# SENS_LEDS.net
KiCad netlist of a schematic drawn in Altium Designer
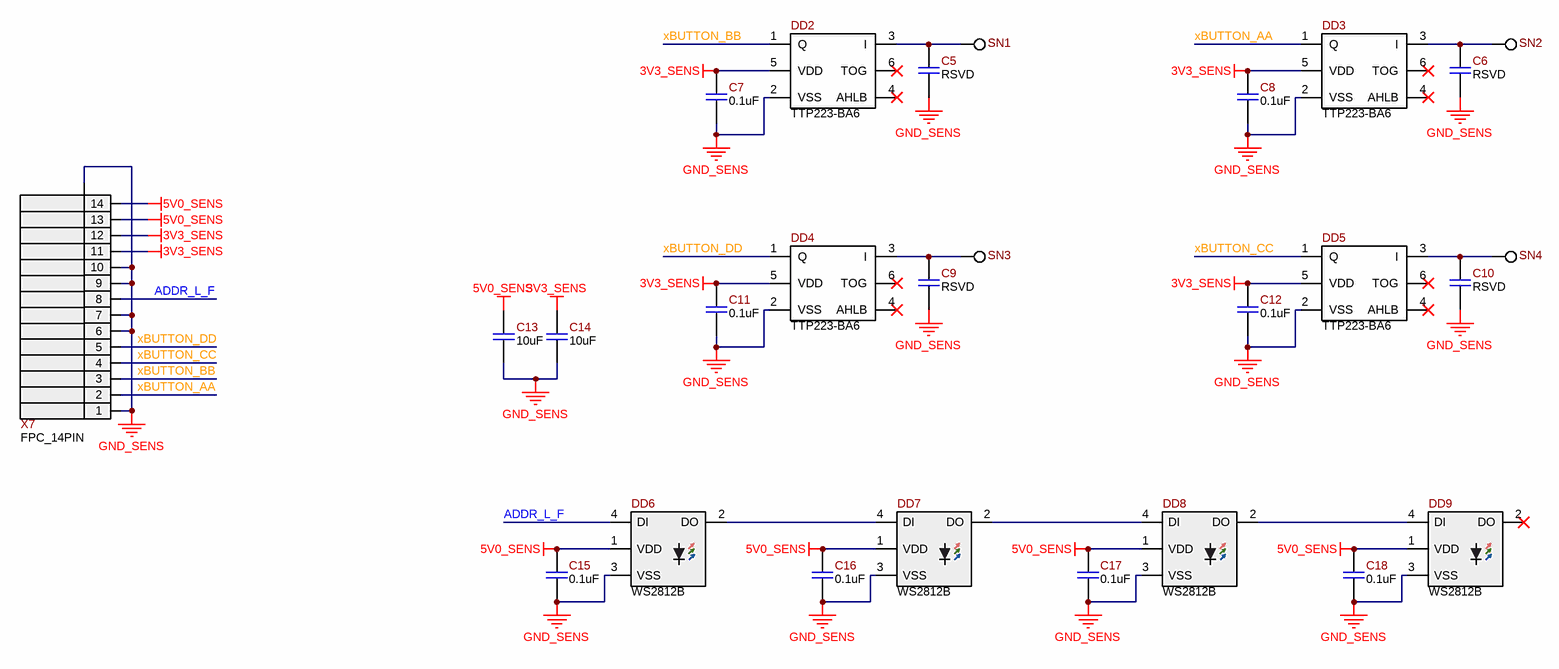
[diagram p0: SENS+LEDS.SchDoc]

(export (version "E")
  (design (tool "Eeschema 10.0.6"))
  (components
    (comp (ref "C5")
      (value "RSVD")
      (footprint "C0402(1005)")
      (description "CAP CER 0.1UF 25V X7R 0402")
      (fields (field (name "PART NUMBER") "0.1uF  25V C0402") (field (name "TOLERANCE") "±10%"))
      (libsource (lib "Database") (part "Capacitor_Ceramic"))
    )
    (comp (ref "C6")
      (value "RSVD")
      (footprint "C0402(1005)")
      (description "CAP CER 0.1UF 25V X7R 0402")
      (fields (field (name "PART NUMBER") "0.1uF  25V C0402") (field (name "TOLERANCE") "±10%"))
      (libsource (lib "Database") (part "Capacitor_Ceramic"))
    )
    (comp (ref "C7")
      (value "0.1uF")
      (footprint "C0402(1005)")
      (description "CAP CER 0.1UF 25V X7R 0402")
      (fields (field (name "PART NUMBER") "0.1uF  25V C0402") (field (name "TOLERANCE") "±10%"))
      (libsource (lib "Database") (part "Capacitor_Ceramic"))
    )
    (comp (ref "C8")
      (value "0.1uF")
      (footprint "C0402(1005)")
      (description "CAP CER 0.1UF 25V X7R 0402")
      (fields (field (name "PART NUMBER") "0.1uF  25V C0402") (field (name "TOLERANCE") "±10%"))
      (libsource (lib "Database") (part "Capacitor_Ceramic"))
    )
    (comp (ref "C9")
      (value "RSVD")
      (footprint "C0402(1005)")
      (description "CAP CER 0.1UF 25V X7R 0402")
      (fields (field (name "PART NUMBER") "0.1uF  25V C0402") (field (name "TOLERANCE") "±10%"))
      (libsource (lib "Database") (part "Capacitor_Ceramic"))
    )
    (comp (ref "C10")
      (value "RSVD")
      (footprint "C0402(1005)")
      (description "CAP CER 0.1UF 25V X7R 0402")
      (fields (field (name "PART NUMBER") "0.1uF  25V C0402") (field (name "TOLERANCE") "±10%"))
      (libsource (lib "Database") (part "Capacitor_Ceramic"))
    )
    (comp (ref "C11")
      (value "0.1uF")
      (footprint "C0402(1005)")
      (description "CAP CER 0.1UF 25V X7R 0402")
      (fields (field (name "PART NUMBER") "0.1uF  25V C0402") (field (name "TOLERANCE") "±10%"))
      (libsource (lib "Database") (part "Capacitor_Ceramic"))
    )
    (comp (ref "C12")
      (value "0.1uF")
      (footprint "C0402(1005)")
      (description "CAP CER 0.1UF 25V X7R 0402")
      (fields (field (name "PART NUMBER") "0.1uF  25V C0402") (field (name "TOLERANCE") "±10%"))
      (libsource (lib "Database") (part "Capacitor_Ceramic"))
    )
    (comp (ref "C13")
      (value "10uF")
      (footprint "C0402(1005)")
      (description "CAP CER 10UF 6.3V X6S 0402")
      (fields (field (name "PART NUMBER") "10uF  6.3V C0402") (field (name "TOLERANCE") "±20%"))
      (libsource (lib "Database") (part "Capacitor_Ceramic"))
    )
    (comp (ref "C14")
      (value "10uF")
      (footprint "C0402(1005)")
      (description "CAP CER 10UF 6.3V X6S 0402")
      (fields (field (name "PART NUMBER") "10uF  6.3V C0402") (field (name "TOLERANCE") "±20%"))
      (libsource (lib "Database") (part "Capacitor_Ceramic"))
    )
    (comp (ref "C15")
      (value "0.1uF")
      (footprint "C0402(1005)")
      (description "CAP CER 0.1UF 25V X7R 0402")
      (fields (field (name "PART NUMBER") "0.1uF  25V C0402") (field (name "TOLERANCE") "±10%"))
      (libsource (lib "Database") (part "Capacitor_Ceramic"))
    )
    (comp (ref "C16")
      (value "0.1uF")
      (footprint "C0402(1005)")
      (description "CAP CER 0.1UF 25V X7R 0402")
      (fields (field (name "PART NUMBER") "0.1uF  25V C0402") (field (name "TOLERANCE") "±10%"))
      (libsource (lib "Database") (part "Capacitor_Ceramic"))
    )
    (comp (ref "C17")
      (value "0.1uF")
      (footprint "C0402(1005)")
      (description "CAP CER 0.1UF 25V X7R 0402")
      (fields (field (name "PART NUMBER") "0.1uF  25V C0402") (field (name "TOLERANCE") "±10%"))
      (libsource (lib "Database") (part "Capacitor_Ceramic"))
    )
    (comp (ref "C18")
      (value "0.1uF")
      (footprint "C0402(1005)")
      (description "CAP CER 0.1UF 25V X7R 0402")
      (fields (field (name "PART NUMBER") "0.1uF  25V C0402") (field (name "TOLERANCE") "±10%"))
      (libsource (lib "Database") (part "Capacitor_Ceramic"))
    )
    (comp (ref "DD2")
      (value "TTP223-BA6")
      (footprint "SOT23-6L")
      (description "TOUCH SENSOR")
      (fields (field (name "MANUFACTURER") "TonTouch"))
      (libsource (lib "Database") (part "TTP223-BA6"))
    )
    (comp (ref "DD3")
      (value "TTP223-BA6")
      (footprint "SOT23-6L")
      (description "TOUCH SENSOR")
      (fields (field (name "MANUFACTURER") "TonTouch"))
      (libsource (lib "Database") (part "TTP223-BA6"))
    )
    (comp (ref "DD4")
      (value "TTP223-BA6")
      (footprint "SOT23-6L")
      (description "TOUCH SENSOR")
      (fields (field (name "MANUFACTURER") "TonTouch"))
      (libsource (lib "Database") (part "TTP223-BA6"))
    )
    (comp (ref "DD5")
      (value "TTP223-BA6")
      (footprint "SOT23-6L")
      (description "TOUCH SENSOR")
      (fields (field (name "MANUFACTURER") "TonTouch"))
      (libsource (lib "Database") (part "TTP223-BA6"))
    )
    (comp (ref "DD6")
      (value "WS2812B")
      (footprint "WS2812")
      (description "ADDRESS LED DISCR SER RGB")
      (fields (field (name "MANUFACTURER") "Worldsemi"))
      (libsource (lib "Database") (part "WS2812"))
    )
    (comp (ref "DD7")
      (value "WS2812B")
      (footprint "WS2812")
      (description "ADDRESS LED DISCR SER RGB")
      (fields (field (name "MANUFACTURER") "Worldsemi"))
      (libsource (lib "Database") (part "WS2812"))
    )
    (comp (ref "DD8")
      (value "WS2812B")
      (footprint "WS2812")
      (description "ADDRESS LED DISCR SER RGB")
      (fields (field (name "MANUFACTURER") "Worldsemi"))
      (libsource (lib "Database") (part "WS2812"))
    )
    (comp (ref "DD9")
      (value "WS2812B")
      (footprint "WS2812")
      (description "ADDRESS LED DISCR SER RGB")
      (fields (field (name "MANUFACTURER") "Worldsemi"))
      (libsource (lib "") (part "WS2812_1"))
    )
    (comp (ref "SN1")
      (value "PAD-1.1mm")
      (footprint "PAD-1.1mm")
      (description "1.1mm Pad for Plug-In or Receptacle")
      (fields (field (name "MANUFACTURER") "NONE"))
      (libsource (lib "AjaxLibrary") (part "Pad"))
    )
    (comp (ref "SN2")
      (value "PAD-1.1mm")
      (footprint "PAD-1.1mm")
      (description "1.1mm Pad for Plug-In or Receptacle")
      (fields (field (name "MANUFACTURER") "NONE"))
      (libsource (lib "AjaxLibrary") (part "Pad"))
    )
    (comp (ref "SN3")
      (value "PAD-1.1mm")
      (footprint "PAD-1.1mm")
      (description "1.1mm Pad for Plug-In or Receptacle")
      (fields (field (name "MANUFACTURER") "NONE"))
      (libsource (lib "AjaxLibrary") (part "Pad"))
    )
    (comp (ref "SN4")
      (value "PAD-1.1mm")
      (footprint "PAD-1.1mm")
      (description "1.1mm Pad for Plug-In or Receptacle")
      (fields (field (name "MANUFACTURER") "NONE"))
      (libsource (lib "AjaxLibrary") (part "Pad"))
    )
    (comp (ref "X7")
      (value "FPC_14PIN")
      (footprint "FPC-14-0.5mm")
      (description "FPC CONNECTOR")
      (libsource (lib "Database") (part "CON_14_MP"))
    )
  )
  (nets
    (net (code "1") (name "/ADDR_L_F") (class "Default")
      (node (ref "DD6") (pin "4") (pinfunction "DI_4") (pintype "passive"))
      (node (ref "X7") (pin "8") (pinfunction "8_8") (pintype "passive"))
    )
    (net (code "2") (name "/xBUTTON_AA") (class "Default")
      (node (ref "DD3") (pin "1") (pinfunction "Q_1") (pintype "passive"))
      (node (ref "X7") (pin "2") (pinfunction "2_2") (pintype "passive"))
    )
    (net (code "3") (name "/xBUTTON_BB") (class "Default")
      (node (ref "DD2") (pin "1") (pinfunction "Q_1") (pintype "passive"))
      (node (ref "X7") (pin "3") (pinfunction "3_3") (pintype "passive"))
    )
    (net (code "4") (name "/xBUTTON_CC") (class "Default")
      (node (ref "DD5") (pin "1") (pinfunction "Q_1") (pintype "passive"))
      (node (ref "X7") (pin "4") (pinfunction "4_4") (pintype "passive"))
    )
    (net (code "5") (name "/xBUTTON_DD") (class "Default")
      (node (ref "DD4") (pin "1") (pinfunction "Q_1") (pintype "passive"))
      (node (ref "X7") (pin "5") (pinfunction "5_5") (pintype "passive"))
    )
    (net (code "6") (name "3V3_SENS") (class "Default")
      (node (ref "C11") (pin "1") (pinfunction "1_1") (pintype "passive"))
      (node (ref "C12") (pin "1") (pinfunction "1_1") (pintype "passive"))
      (node (ref "C14") (pin "2") (pinfunction "2_2") (pintype "passive"))
      (node (ref "C7") (pin "1") (pinfunction "1_1") (pintype "passive"))
      (node (ref "C8") (pin "1") (pinfunction "1_1") (pintype "passive"))
      (node (ref "DD2") (pin "5") (pinfunction "VDD_5") (pintype "passive"))
      (node (ref "DD3") (pin "5") (pinfunction "VDD_5") (pintype "passive"))
      (node (ref "DD4") (pin "5") (pinfunction "VDD_5") (pintype "passive"))
      (node (ref "DD5") (pin "5") (pinfunction "VDD_5") (pintype "passive"))
      (node (ref "X7") (pin "11") (pinfunction "11_11") (pintype "passive"))
      (node (ref "X7") (pin "12") (pinfunction "12_12") (pintype "passive"))
    )
    (net (code "7") (name "5V0_SENS") (class "Default")
      (node (ref "C13") (pin "2") (pinfunction "2_2") (pintype "passive"))
      (node (ref "C15") (pin "1") (pinfunction "1_1") (pintype "passive"))
      (node (ref "C16") (pin "1") (pinfunction "1_1") (pintype "passive"))
      (node (ref "C17") (pin "1") (pinfunction "1_1") (pintype "passive"))
      (node (ref "C18") (pin "1") (pinfunction "1_1") (pintype "passive"))
      (node (ref "DD6") (pin "1") (pinfunction "VDD_1") (pintype "passive"))
      (node (ref "DD7") (pin "1") (pinfunction "VDD_1") (pintype "passive"))
      (node (ref "DD8") (pin "1") (pinfunction "VDD_1") (pintype "passive"))
      (node (ref "DD9") (pin "1") (pinfunction "VDD_1") (pintype "passive"))
      (node (ref "X7") (pin "13") (pinfunction "13_13") (pintype "passive"))
      (node (ref "X7") (pin "14") (pinfunction "14_14") (pintype "passive"))
    )
    (net (code "8") (name "GND_SENS") (class "Default")
      (node (ref "C10") (pin "2") (pinfunction "2_2") (pintype "passive"))
      (node (ref "C11") (pin "2") (pinfunction "2_2") (pintype "passive"))
      (node (ref "C12") (pin "2") (pinfunction "2_2") (pintype "passive"))
      (node (ref "C13") (pin "1") (pinfunction "1_1") (pintype "passive"))
      (node (ref "C14") (pin "1") (pinfunction "1_1") (pintype "passive"))
      (node (ref "C15") (pin "2") (pinfunction "2_2") (pintype "passive"))
      (node (ref "C16") (pin "2") (pinfunction "2_2") (pintype "passive"))
      (node (ref "C17") (pin "2") (pinfunction "2_2") (pintype "passive"))
      (node (ref "C18") (pin "2") (pinfunction "2_2") (pintype "passive"))
      (node (ref "C5") (pin "2") (pinfunction "2_2") (pintype "passive"))
      (node (ref "C6") (pin "2") (pinfunction "2_2") (pintype "passive"))
      (node (ref "C7") (pin "2") (pinfunction "2_2") (pintype "passive"))
      (node (ref "C8") (pin "2") (pinfunction "2_2") (pintype "passive"))
      (node (ref "C9") (pin "2") (pinfunction "2_2") (pintype "passive"))
      (node (ref "DD2") (pin "2") (pinfunction "VSS_2") (pintype "passive"))
      (node (ref "DD3") (pin "2") (pinfunction "VSS_2") (pintype "passive"))
      (node (ref "DD4") (pin "2") (pinfunction "VSS_2") (pintype "passive"))
      (node (ref "DD5") (pin "2") (pinfunction "VSS_2") (pintype "passive"))
      (node (ref "DD6") (pin "3") (pinfunction "VSS_3") (pintype "passive"))
      (node (ref "DD7") (pin "3") (pinfunction "VSS_3") (pintype "passive"))
      (node (ref "DD8") (pin "3") (pinfunction "VSS_3") (pintype "passive"))
      (node (ref "DD9") (pin "3") (pinfunction "VSS_3") (pintype "passive"))
      (node (ref "X7") (pin "1") (pinfunction "1_1") (pintype "passive"))
      (node (ref "X7") (pin "10") (pinfunction "10_10") (pintype "passive"))
      (node (ref "X7") (pin "15") (pinfunction "15_15") (pintype "passive"))
      (node (ref "X7") (pin "6") (pinfunction "6_6") (pintype "passive"))
      (node (ref "X7") (pin "7") (pinfunction "7_7") (pintype "passive"))
      (node (ref "X7") (pin "9") (pinfunction "9_9") (pintype "passive"))
    )
    (net (code "9") (name "Net-(DD2-I)") (class "Default")
      (node (ref "C5") (pin "1") (pinfunction "1_1") (pintype "passive"))
      (node (ref "DD2") (pin "3") (pinfunction "I_3") (pintype "passive"))
      (node (ref "SN1") (pin "1") (pintype "passive"))
    )
    (net (code "10") (name "Net-(DD3-I)") (class "Default")
      (node (ref "C6") (pin "1") (pinfunction "1_1") (pintype "passive"))
      (node (ref "DD3") (pin "3") (pinfunction "I_3") (pintype "passive"))
      (node (ref "SN2") (pin "1") (pintype "passive"))
    )
    (net (code "11") (name "Net-(DD4-I)") (class "Default")
      (node (ref "C9") (pin "1") (pinfunction "1_1") (pintype "passive"))
      (node (ref "DD4") (pin "3") (pinfunction "I_3") (pintype "passive"))
      (node (ref "SN3") (pin "1") (pintype "passive"))
    )
    (net (code "12") (name "Net-(DD5-I)") (class "Default")
      (node (ref "C10") (pin "1") (pinfunction "1_1") (pintype "passive"))
      (node (ref "DD5") (pin "3") (pinfunction "I_3") (pintype "passive"))
      (node (ref "SN4") (pin "1") (pintype "passive"))
    )
    (net (code "13") (name "Net-(DD6-DO)") (class "Default")
      (node (ref "DD6") (pin "2") (pinfunction "DO_2") (pintype "passive"))
      (node (ref "DD7") (pin "4") (pinfunction "DI_4") (pintype "passive"))
    )
    (net (code "14") (name "Net-(DD7-DO)") (class "Default")
      (node (ref "DD7") (pin "2") (pinfunction "DO_2") (pintype "passive"))
      (node (ref "DD8") (pin "4") (pinfunction "DI_4") (pintype "passive"))
    )
    (net (code "15") (name "Net-(DD8-DO)") (class "Default")
      (node (ref "DD8") (pin "2") (pinfunction "DO_2") (pintype "passive"))
      (node (ref "DD9") (pin "4") (pinfunction "DI_4") (pintype "passive"))
    )
    (net (code "16") (name "unconnected-(DD2-AHLB-Pad4)") (class "Default")
      (node (ref "DD2") (pin "4") (pinfunction "AHLB_4") (pintype "passive+no_connect"))
    )
    (net (code "17") (name "unconnected-(DD2-TOG-Pad6)") (class "Default")
      (node (ref "DD2") (pin "6") (pinfunction "TOG_6") (pintype "passive+no_connect"))
    )
    (net (code "18") (name "unconnected-(DD3-AHLB-Pad4)") (class "Default")
      (node (ref "DD3") (pin "4") (pinfunction "AHLB_4") (pintype "passive+no_connect"))
    )
    (net (code "19") (name "unconnected-(DD3-TOG-Pad6)") (class "Default")
      (node (ref "DD3") (pin "6") (pinfunction "TOG_6") (pintype "passive+no_connect"))
    )
    (net (code "20") (name "unconnected-(DD4-AHLB-Pad4)") (class "Default")
      (node (ref "DD4") (pin "4") (pinfunction "AHLB_4") (pintype "passive+no_connect"))
    )
    (net (code "21") (name "unconnected-(DD4-TOG-Pad6)") (class "Default")
      (node (ref "DD4") (pin "6") (pinfunction "TOG_6") (pintype "passive+no_connect"))
    )
    (net (code "22") (name "unconnected-(DD5-AHLB-Pad4)") (class "Default")
      (node (ref "DD5") (pin "4") (pinfunction "AHLB_4") (pintype "passive+no_connect"))
    )
    (net (code "23") (name "unconnected-(DD5-TOG-Pad6)") (class "Default")
      (node (ref "DD5") (pin "6") (pinfunction "TOG_6") (pintype "passive+no_connect"))
    )
    (net (code "24") (name "unconnected-(DD9-DO-Pad2)") (class "Default")
      (node (ref "DD9") (pin "2") (pinfunction "DO_2") (pintype "passive+no_connect"))
    )
  )
)
